# 2_mb_conn.net
KiCad netlist of a schematic drawn in Altium Designer
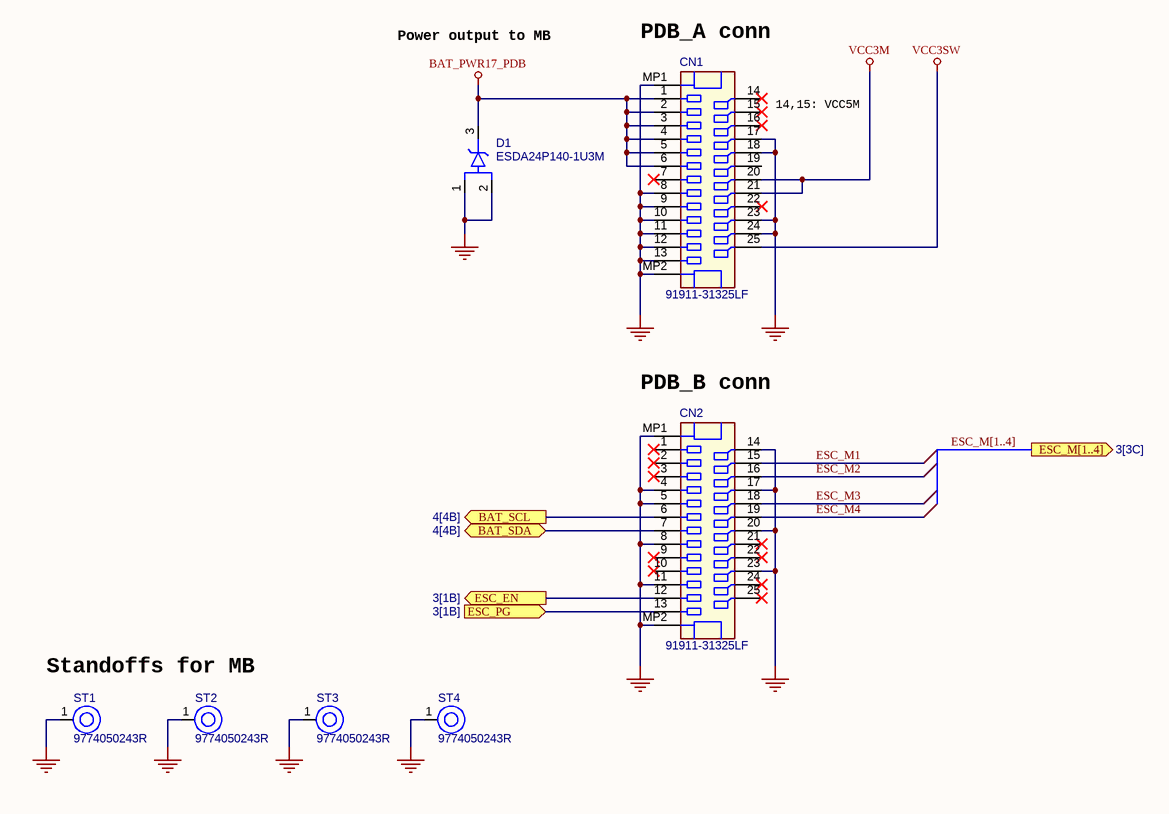
[diagram p0: 2_mb_conn.SchDoc]

(export (version "E")
  (design (tool "Eeschema 10.0.6"))
  (components
    (comp (ref "CN1")
      (value "91911-31325LF")
      (footprint "AMPH-91911-31325_V")
      (description "Header, Pitch 1 mm, 25 Position, Height 5 mm, -55 to 130 degC")
      (libsource (lib "<Company> Server") (part "CMP-00168-4"))
    )
    (comp (ref "CN2")
      (value "91911-31325LF")
      (footprint "AMPH-91911-31325_V")
      (description "Header, Pitch 1 mm, 25 Position, Height 5 mm, -55 to 130 degC")
      (libsource (lib "<Company> Server") (part "CMP-00168-4"))
    )
    (comp (ref "D1")
      (value "ESDA24P140-1U3M")
      (footprint "STM-QFN3")
      (description "TVS diode, 4500W, 22V standoff, 29.5V clamp")
      (libsource (lib "<Company> Server") (part "D-TVS-AAK-3"))
    )
    (comp (ref "ST1")
      (value "9774050243R")
      (footprint "WE-9774050243R_V")
      (description "WA-SMSI SMT Steel Spacer, M2 Thread Internal, Tin, RoHS, Tape and Reel")
      (libsource (lib "<Company> Server") (part "CMP-00028-00000-1"))
    )
    (comp (ref "ST2")
      (value "9774050243R")
      (footprint "WE-9774050243R_V")
      (description "WA-SMSI SMT Steel Spacer, M2 Thread Internal, Tin, RoHS, Tape and Reel")
      (libsource (lib "<Company> Server") (part "CMP-00028-00000-1"))
    )
    (comp (ref "ST3")
      (value "9774050243R")
      (footprint "WE-9774050243R_V")
      (description "WA-SMSI SMT Steel Spacer, M2 Thread Internal, Tin, RoHS, Tape and Reel")
      (libsource (lib "<Company> Server") (part "CMP-00028-00000-1"))
    )
    (comp (ref "ST4")
      (value "9774050243R")
      (footprint "WE-9774050243R_V")
      (description "WA-SMSI SMT Steel Spacer, M2 Thread Internal, Tin, RoHS, Tape and Reel")
      (libsource (lib "<Company> Server") (part "CMP-00028-00000-1"))
    )
  )
  (nets
    (net (code "1") (name "/BAT_SCL") (class "Default")
      (node (ref "CN2") (pin "6") (pinfunction "6_6") (pintype "passive"))
    )
    (net (code "2") (name "/BAT_SDA") (class "Default")
      (node (ref "CN2") (pin "7") (pinfunction "7_7") (pintype "passive"))
    )
    (net (code "3") (name "/ESC_EN") (class "Default")
      (node (ref "CN2") (pin "12") (pinfunction "12_12") (pintype "passive"))
    )
    (net (code "4") (name "/ESC_M1") (class "Default")
      (node (ref "CN2") (pin "15") (pinfunction "15_15") (pintype "passive"))
    )
    (net (code "5") (name "/ESC_M2") (class "Default")
      (node (ref "CN2") (pin "16") (pinfunction "16_16") (pintype "passive"))
    )
    (net (code "6") (name "/ESC_M3") (class "Default")
      (node (ref "CN2") (pin "18") (pinfunction "18_18") (pintype "passive"))
    )
    (net (code "7") (name "/ESC_M4") (class "Default")
      (node (ref "CN2") (pin "19") (pinfunction "19_19") (pintype "passive"))
    )
    (net (code "9") (name "/ESC_PG") (class "Default")
      (node (ref "CN2") (pin "13") (pinfunction "13_13") (pintype "passive"))
    )
    (net (code "10") (name "BAT_PWR17_PDB") (class "Default")
      (node (ref "CN1") (pin "1") (pinfunction "1_1") (pintype "passive"))
      (node (ref "CN1") (pin "2") (pinfunction "2_2") (pintype "passive"))
      (node (ref "CN1") (pin "3") (pinfunction "3_3") (pintype "passive"))
      (node (ref "CN1") (pin "4") (pinfunction "4_4") (pintype "passive"))
      (node (ref "CN1") (pin "5") (pinfunction "5_5") (pintype "passive"))
      (node (ref "CN1") (pin "6") (pinfunction "6_6") (pintype "passive"))
      (node (ref "D1") (pin "3") (pinfunction "K_3") (pintype "passive"))
    )
    (net (code "11") (name "GND") (class "Default")
      (node (ref "CN1") (pin "10") (pinfunction "10_10") (pintype "passive"))
      (node (ref "CN1") (pin "11") (pinfunction "11_11") (pintype "passive"))
      (node (ref "CN1") (pin "12") (pinfunction "12_12") (pintype "passive"))
      (node (ref "CN1") (pin "13") (pinfunction "13_13") (pintype "passive"))
      (node (ref "CN1") (pin "17") (pinfunction "17_17") (pintype "passive"))
      (node (ref "CN1") (pin "18") (pinfunction "18_18") (pintype "passive"))
      (node (ref "CN1") (pin "23") (pinfunction "23_23") (pintype "passive"))
      (node (ref "CN1") (pin "24") (pinfunction "24_24") (pintype "passive"))
      (node (ref "CN1") (pin "8") (pinfunction "8_8") (pintype "passive"))
      (node (ref "CN1") (pin "9") (pinfunction "9_9") (pintype "passive"))
      (node (ref "CN1") (pin "MP1") (pinfunction "MP1_MP1") (pintype "passive"))
      (node (ref "CN1") (pin "MP2") (pinfunction "MP2_MP2") (pintype "passive"))
      (node (ref "CN2") (pin "11") (pinfunction "11_11") (pintype "passive"))
      (node (ref "CN2") (pin "14") (pinfunction "14_14") (pintype "passive"))
      (node (ref "CN2") (pin "17") (pinfunction "17_17") (pintype "passive"))
      (node (ref "CN2") (pin "20") (pinfunction "20_20") (pintype "passive"))
      (node (ref "CN2") (pin "23") (pinfunction "23_23") (pintype "passive"))
      (node (ref "CN2") (pin "4") (pinfunction "4_4") (pintype "passive"))
      (node (ref "CN2") (pin "5") (pinfunction "5_5") (pintype "passive"))
      (node (ref "CN2") (pin "8") (pinfunction "8_8") (pintype "passive"))
      (node (ref "CN2") (pin "MP1") (pinfunction "MP1_MP1") (pintype "passive"))
      (node (ref "CN2") (pin "MP2") (pinfunction "MP2_MP2") (pintype "passive"))
      (node (ref "D1") (pin "1") (pinfunction "A_1") (pintype "passive"))
      (node (ref "D1") (pin "2") (pinfunction "A_2") (pintype "passive"))
      (node (ref "ST1") (pin "1") (pinfunction "H1_1") (pintype "passive"))
      (node (ref "ST2") (pin "1") (pinfunction "H1_1") (pintype "passive"))
      (node (ref "ST3") (pin "1") (pinfunction "H1_1") (pintype "passive"))
      (node (ref "ST4") (pin "1") (pinfunction "H1_1") (pintype "passive"))
    )
    (net (code "12") (name "VCC3M") (class "Default")
      (node (ref "CN1") (pin "20") (pinfunction "20_20") (pintype "passive"))
      (node (ref "CN1") (pin "21") (pinfunction "21_21") (pintype "passive"))
    )
    (net (code "13") (name "VCC3SW") (class "Default")
      (node (ref "CN1") (pin "25") (pinfunction "25_25") (pintype "passive"))
    )
    (net (code "14") (name "unconnected-(CN1-Pad7)") (class "Default")
      (node (ref "CN1") (pin "7") (pinfunction "7_7") (pintype "passive+no_connect"))
    )
    (net (code "15") (name "unconnected-(CN1-Pad14)") (class "Default")
      (node (ref "CN1") (pin "14") (pinfunction "14_14") (pintype "passive+no_connect"))
    )
    (net (code "16") (name "unconnected-(CN1-Pad15)") (class "Default")
      (node (ref "CN1") (pin "15") (pinfunction "15_15") (pintype "passive+no_connect"))
    )
    (net (code "17") (name "unconnected-(CN1-Pad16)") (class "Default")
      (node (ref "CN1") (pin "16") (pinfunction "16_16") (pintype "passive+no_connect"))
    )
    (net (code "18") (name "unconnected-(CN1-Pad19)") (class "Default")
      (node (ref "CN1") (pin "19") (pinfunction "19_19") (pintype "passive"))
    )
    (net (code "19") (name "unconnected-(CN1-Pad22)") (class "Default")
      (node (ref "CN1") (pin "22") (pinfunction "22_22") (pintype "passive+no_connect"))
    )
    (net (code "20") (name "unconnected-(CN2-Pad1)") (class "Default")
      (node (ref "CN2") (pin "1") (pinfunction "1_1") (pintype "passive+no_connect"))
    )
    (net (code "21") (name "unconnected-(CN2-Pad2)") (class "Default")
      (node (ref "CN2") (pin "2") (pinfunction "2_2") (pintype "passive+no_connect"))
    )
    (net (code "22") (name "unconnected-(CN2-Pad3)") (class "Default")
      (node (ref "CN2") (pin "3") (pinfunction "3_3") (pintype "passive+no_connect"))
    )
    (net (code "23") (name "unconnected-(CN2-Pad9)") (class "Default")
      (node (ref "CN2") (pin "9") (pinfunction "9_9") (pintype "passive+no_connect"))
    )
    (net (code "24") (name "unconnected-(CN2-Pad10)") (class "Default")
      (node (ref "CN2") (pin "10") (pinfunction "10_10") (pintype "passive+no_connect"))
    )
    (net (code "25") (name "unconnected-(CN2-Pad21)") (class "Default")
      (node (ref "CN2") (pin "21") (pinfunction "21_21") (pintype "passive+no_connect"))
    )
    (net (code "26") (name "unconnected-(CN2-Pad22)") (class "Default")
      (node (ref "CN2") (pin "22") (pinfunction "22_22") (pintype "passive+no_connect"))
    )
    (net (code "27") (name "unconnected-(CN2-Pad24)") (class "Default")
      (node (ref "CN2") (pin "24") (pinfunction "24_24") (pintype "passive+no_connect"))
    )
    (net (code "28") (name "unconnected-(CN2-Pad25)") (class "Default")
      (node (ref "CN2") (pin "25") (pinfunction "25_25") (pintype "passive+no_connect"))
    )
  )
)
